# TopLevel.net
KiCad netlist of a schematic drawn in Altium Designer
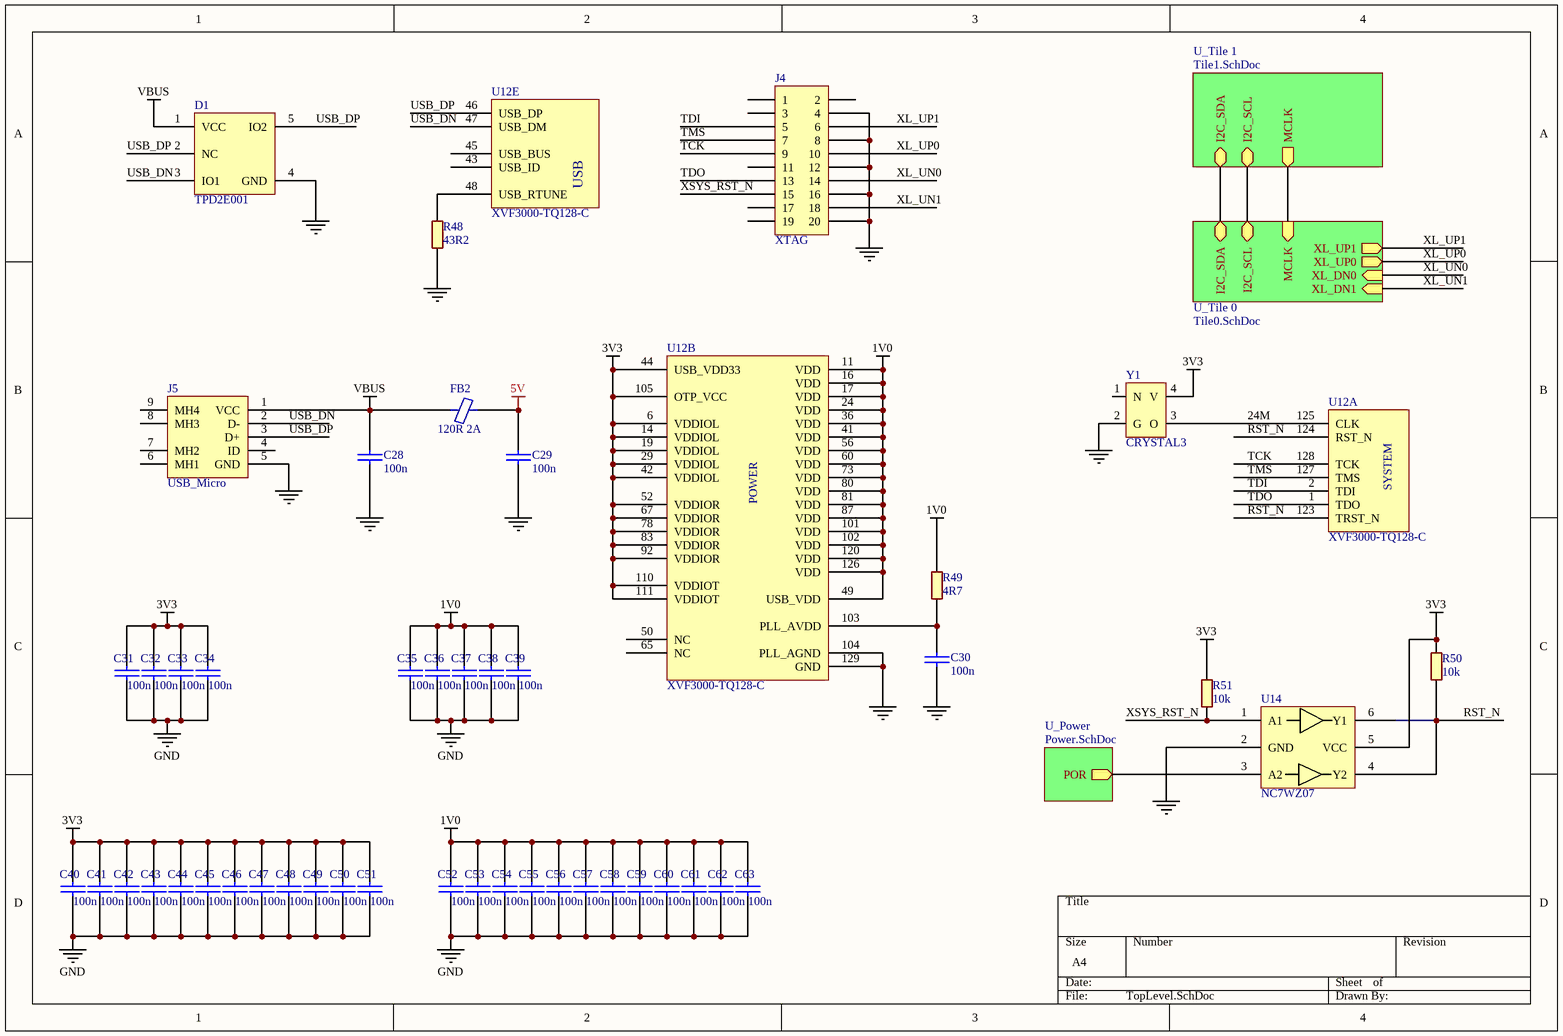
[diagram p0: TopLevel.SchDoc]

(export (version "E")
  (design (tool "Eeschema 10.0.6"))
  (components
    (comp (ref "C28")
      (value "100n")
      (footprint "C0603")
      (description "Capacitor")
      (libsource (lib "Library") (part "CAP"))
    )
    (comp (ref "C29")
      (value "100n")
      (footprint "C0603")
      (description "Capacitor")
      (libsource (lib "Library") (part "CAP"))
    )
    (comp (ref "C30")
      (value "100n")
      (footprint "C0603")
      (description "Capacitor")
      (libsource (lib "Library") (part "CAP"))
    )
    (comp (ref "C31")
      (value "100n")
      (footprint "C0603")
      (description "Capacitor")
      (libsource (lib "Library") (part "CAP"))
    )
    (comp (ref "C32")
      (value "100n")
      (footprint "C0603")
      (description "Capacitor")
      (libsource (lib "Library") (part "CAP"))
    )
    (comp (ref "C33")
      (value "100n")
      (footprint "C0603")
      (description "Capacitor")
      (libsource (lib "Library") (part "CAP"))
    )
    (comp (ref "C34")
      (value "100n")
      (footprint "C0603")
      (description "Capacitor")
      (libsource (lib "Library") (part "CAP"))
    )
    (comp (ref "C35")
      (value "100n")
      (footprint "C0603")
      (description "Capacitor")
      (libsource (lib "Library") (part "CAP"))
    )
    (comp (ref "C36")
      (value "100n")
      (footprint "C0603")
      (description "Capacitor")
      (libsource (lib "Library") (part "CAP"))
    )
    (comp (ref "C37")
      (value "100n")
      (footprint "C0603")
      (description "Capacitor")
      (libsource (lib "Library") (part "CAP"))
    )
    (comp (ref "C38")
      (value "100n")
      (footprint "C0603")
      (description "Capacitor")
      (libsource (lib "Library") (part "CAP"))
    )
    (comp (ref "C39")
      (value "100n")
      (footprint "C0603")
      (description "Capacitor")
      (libsource (lib "Library") (part "CAP"))
    )
    (comp (ref "C40")
      (value "100n")
      (footprint "C0603")
      (description "Capacitor")
      (libsource (lib "Library") (part "CAP"))
    )
    (comp (ref "C41")
      (value "100n")
      (footprint "C0603")
      (description "Capacitor")
      (libsource (lib "Library") (part "CAP"))
    )
    (comp (ref "C42")
      (value "100n")
      (footprint "C0603")
      (description "Capacitor")
      (libsource (lib "Library") (part "CAP"))
    )
    (comp (ref "C43")
      (value "100n")
      (footprint "C0603")
      (description "Capacitor")
      (libsource (lib "Library") (part "CAP"))
    )
    (comp (ref "C44")
      (value "100n")
      (footprint "C0603")
      (description "Capacitor")
      (libsource (lib "Library") (part "CAP"))
    )
    (comp (ref "C45")
      (value "100n")
      (footprint "C0603")
      (description "Capacitor")
      (libsource (lib "Library") (part "CAP"))
    )
    (comp (ref "C46")
      (value "100n")
      (footprint "C0603")
      (description "Capacitor")
      (libsource (lib "Library") (part "CAP"))
    )
    (comp (ref "C47")
      (value "100n")
      (footprint "C0603")
      (description "Capacitor")
      (libsource (lib "Library") (part "CAP"))
    )
    (comp (ref "C48")
      (value "100n")
      (footprint "C0603")
      (description "Capacitor")
      (libsource (lib "Library") (part "CAP"))
    )
    (comp (ref "C49")
      (value "100n")
      (footprint "C0603")
      (description "Capacitor")
      (libsource (lib "Library") (part "CAP"))
    )
    (comp (ref "C50")
      (value "100n")
      (footprint "C0603")
      (description "Capacitor")
      (libsource (lib "Library") (part "CAP"))
    )
    (comp (ref "C51")
      (value "100n")
      (footprint "C0603")
      (description "Capacitor")
      (libsource (lib "Library") (part "CAP"))
    )
    (comp (ref "C52")
      (value "100n")
      (footprint "C0603")
      (description "Capacitor")
      (libsource (lib "Library") (part "CAP"))
    )
    (comp (ref "C53")
      (value "100n")
      (footprint "C0603")
      (description "Capacitor")
      (libsource (lib "Library") (part "CAP"))
    )
    (comp (ref "C54")
      (value "100n")
      (footprint "C0603")
      (description "Capacitor")
      (libsource (lib "Library") (part "CAP"))
    )
    (comp (ref "C55")
      (value "100n")
      (footprint "C0603")
      (description "Capacitor")
      (libsource (lib "Library") (part "CAP"))
    )
    (comp (ref "C56")
      (value "100n")
      (footprint "C0603")
      (description "Capacitor")
      (libsource (lib "Library") (part "CAP"))
    )
    (comp (ref "C57")
      (value "100n")
      (footprint "C0603")
      (description "Capacitor")
      (libsource (lib "Library") (part "CAP"))
    )
    (comp (ref "C58")
      (value "100n")
      (footprint "C0603")
      (description "Capacitor")
      (libsource (lib "Library") (part "CAP"))
    )
    (comp (ref "C59")
      (value "100n")
      (footprint "C0603")
      (description "Capacitor")
      (libsource (lib "Library") (part "CAP"))
    )
    (comp (ref "C60")
      (value "100n")
      (footprint "C0603")
      (description "Capacitor")
      (libsource (lib "Library") (part "CAP"))
    )
    (comp (ref "C61")
      (value "100n")
      (footprint "C0603")
      (description "Capacitor")
      (libsource (lib "Library") (part "CAP"))
    )
    (comp (ref "C62")
      (value "100n")
      (footprint "C0603")
      (description "Capacitor")
      (libsource (lib "Library") (part "CAP"))
    )
    (comp (ref "C63")
      (value "100n")
      (footprint "C0603")
      (description "Capacitor")
      (libsource (lib "Library") (part "CAP"))
    )
    (comp (ref "D1") (value "TPD2E001") (footprint "SOT-5X3") (libsource (lib "Library") (part "TPD2E001")))
    (comp (ref "FB2") (value "120R 2A") (footprint "L0603") (libsource (lib "Library") (part "FB")))
    (comp (ref "J4")
      (value "XTAG")
      (footprint "MHDR2X10")
      (description "Header, 10-Pin, Dual row")
      (fields (field (name "PUBLISHER") "Altium Limited"))
      (libsource (lib "Miscellaneous Connectors") (part "MHDR2X10"))
    )
    (comp (ref "J5")
      (value "USB_Micro")
      (footprint "USB-MICRO5")
      (description "USB micro female SMT with 4 fixed foot")
      (libsource (lib "Library") (part "USB_Micro_5S_B"))
    )
    (comp (ref "R48")
      (value "43R2")
      (footprint "R0603")
      (description "RES")
      (libsource (lib "Library") (part "R"))
    )
    (comp (ref "R49")
      (value "4R7")
      (footprint "R0603")
      (description "RES")
      (libsource (lib "Library") (part "R"))
    )
    (comp (ref "R50")
      (value "10k")
      (footprint "R0603")
      (description "RES")
      (libsource (lib "Library") (part "R"))
    )
    (comp (ref "R51")
      (value "10k")
      (footprint "R0603")
      (description "RES")
      (libsource (lib "Library") (part "R"))
    )
    (comp (ref "U12")
      (value "XVF3000-TQ128-C")
      (footprint "LQFP-128 - VSS")
      (libsource (lib "Library") (part "XVF3000-TQ128-C"))
    )
    (comp (ref "U14") (value "NC7WZ07") (footprint "SC70-6") (libsource (lib "Library") (part "NC7WZ07")))
    (comp (ref "Y1") (value "CRYSTAL3") (footprint "JT3225") (libsource (lib "Library") (part "CRYSTAL3")))
  )
  (nets
    (net (code "1") (name "/24M") (class "Default")
      (node (ref "U12") (pin "125") (pinfunction "CLK_125") (pintype "passive"))
      (node (ref "Y1") (pin "3") (pinfunction "O_3") (pintype "passive"))
    )
    (net (code "5") (name "/POR") (class "Default")
      (node (ref "U14") (pin "3") (pinfunction "A2_3") (pintype "passive"))
    )
    (net (code "6") (name "/RST_N") (class "Default")
      (node (ref "R50") (pin "1") (pinfunction "1_1") (pintype "passive"))
      (node (ref "U12") (pin "123") (pinfunction "TRST_N_123") (pintype "passive"))
      (node (ref "U12") (pin "124") (pinfunction "RST_N_124") (pintype "passive"))
      (node (ref "U14") (pin "4") (pinfunction "Y2_4") (pintype "passive"))
      (node (ref "U14") (pin "6") (pinfunction "Y1_6") (pintype "passive"))
    )
    (net (code "7") (name "/TCK") (class "Default")
      (node (ref "J4") (pin "9") (pinfunction "9_9") (pintype "passive"))
      (node (ref "U12") (pin "128") (pinfunction "TCK_128") (pintype "passive"))
    )
    (net (code "8") (name "/TDI") (class "Default")
      (node (ref "J4") (pin "5") (pinfunction "5_5") (pintype "passive"))
      (node (ref "U12") (pin "2") (pinfunction "TDI_2") (pintype "passive"))
    )
    (net (code "9") (name "/TDO") (class "Default")
      (node (ref "J4") (pin "13") (pinfunction "13_13") (pintype "passive"))
      (node (ref "U12") (pin "1") (pinfunction "TDO_1") (pintype "passive"))
    )
    (net (code "10") (name "/TMS") (class "Default")
      (node (ref "J4") (pin "7") (pinfunction "7_7") (pintype "passive"))
      (node (ref "U12") (pin "127") (pinfunction "TMS_127") (pintype "passive"))
    )
    (net (code "11") (name "/USB_DN") (class "Default")
      (node (ref "D1") (pin "3") (pinfunction "IO1_3") (pintype "passive"))
      (node (ref "J5") (pin "2") (pinfunction "D-_2") (pintype "passive"))
      (node (ref "U12") (pin "47") (pinfunction "USB_DM_47") (pintype "passive"))
    )
    (net (code "12") (name "/USB_DP") (class "Default")
      (node (ref "D1") (pin "2") (pinfunction "NC_2") (pintype "passive"))
      (node (ref "D1") (pin "5") (pinfunction "IO2_5") (pintype "passive"))
      (node (ref "J5") (pin "3") (pinfunction "D+_3") (pintype "passive"))
      (node (ref "U12") (pin "46") (pinfunction "USB_DP_46") (pintype "passive"))
    )
    (net (code "13") (name "/XL_UN0") (class "Default")
      (node (ref "J4") (pin "14") (pinfunction "14_14") (pintype "passive"))
    )
    (net (code "14") (name "/XL_UN1") (class "Default")
      (node (ref "J4") (pin "18") (pinfunction "18_18") (pintype "passive"))
    )
    (net (code "15") (name "/XL_UP0") (class "Default")
      (node (ref "J4") (pin "10") (pinfunction "10_10") (pintype "passive"))
    )
    (net (code "16") (name "/XL_UP1") (class "Default")
      (node (ref "J4") (pin "6") (pinfunction "6_6") (pintype "passive"))
    )
    (net (code "17") (name "/XSYS_RST_N") (class "Default")
      (node (ref "J4") (pin "15") (pinfunction "15_15") (pintype "passive"))
      (node (ref "R51") (pin "1") (pinfunction "1_1") (pintype "passive"))
      (node (ref "U14") (pin "1") (pinfunction "A1_1") (pintype "passive"))
    )
    (net (code "18") (name "1V0") (class "Default")
      (node (ref "C35") (pin "1") (pinfunction "1_1") (pintype "passive"))
      (node (ref "C36") (pin "1") (pinfunction "1_1") (pintype "passive"))
      (node (ref "C37") (pin "1") (pinfunction "1_1") (pintype "passive"))
      (node (ref "C38") (pin "1") (pinfunction "1_1") (pintype "passive"))
      (node (ref "C39") (pin "1") (pinfunction "1_1") (pintype "passive"))
      (node (ref "C52") (pin "1") (pinfunction "1_1") (pintype "passive"))
      (node (ref "C53") (pin "1") (pinfunction "1_1") (pintype "passive"))
      (node (ref "C54") (pin "1") (pinfunction "1_1") (pintype "passive"))
      (node (ref "C55") (pin "1") (pinfunction "1_1") (pintype "passive"))
      (node (ref "C56") (pin "1") (pinfunction "1_1") (pintype "passive"))
      (node (ref "C57") (pin "1") (pinfunction "1_1") (pintype "passive"))
      (node (ref "C58") (pin "1") (pinfunction "1_1") (pintype "passive"))
      (node (ref "C59") (pin "1") (pinfunction "1_1") (pintype "passive"))
      (node (ref "C60") (pin "1") (pinfunction "1_1") (pintype "passive"))
      (node (ref "C61") (pin "1") (pinfunction "1_1") (pintype "passive"))
      (node (ref "C62") (pin "1") (pinfunction "1_1") (pintype "passive"))
      (node (ref "C63") (pin "1") (pinfunction "1_1") (pintype "passive"))
      (node (ref "R49") (pin "2") (pinfunction "2_2") (pintype "passive"))
      (node (ref "U12") (pin "101") (pinfunction "VDD_101") (pintype "passive"))
      (node (ref "U12") (pin "102") (pinfunction "VDD_102") (pintype "passive"))
      (node (ref "U12") (pin "11") (pinfunction "VDD_11") (pintype "passive"))
      (node (ref "U12") (pin "120") (pinfunction "VDD_120") (pintype "passive"))
      (node (ref "U12") (pin "126") (pinfunction "VDD_126") (pintype "passive"))
      (node (ref "U12") (pin "16") (pinfunction "VDD_16") (pintype "passive"))
      (node (ref "U12") (pin "17") (pinfunction "VDD_17") (pintype "passive"))
      (node (ref "U12") (pin "24") (pinfunction "VDD_24") (pintype "passive"))
      (node (ref "U12") (pin "36") (pinfunction "VDD_36") (pintype "passive"))
      (node (ref "U12") (pin "41") (pinfunction "VDD_41") (pintype "passive"))
      (node (ref "U12") (pin "49") (pinfunction "USB_VDD_49") (pintype "passive"))
      (node (ref "U12") (pin "56") (pinfunction "VDD_56") (pintype "passive"))
      (node (ref "U12") (pin "60") (pinfunction "VDD_60") (pintype "passive"))
      (node (ref "U12") (pin "73") (pinfunction "VDD_73") (pintype "passive"))
      (node (ref "U12") (pin "80") (pinfunction "VDD_80") (pintype "passive"))
      (node (ref "U12") (pin "81") (pinfunction "VDD_81") (pintype "passive"))
      (node (ref "U12") (pin "87") (pinfunction "VDD_87") (pintype "passive"))
    )
    (net (code "19") (name "3V3") (class "Default")
      (node (ref "C31") (pin "1") (pinfunction "1_1") (pintype "passive"))
      (node (ref "C32") (pin "1") (pinfunction "1_1") (pintype "passive"))
      (node (ref "C33") (pin "1") (pinfunction "1_1") (pintype "passive"))
      (node (ref "C34") (pin "1") (pinfunction "1_1") (pintype "passive"))
      (node (ref "C40") (pin "1") (pinfunction "1_1") (pintype "passive"))
      (node (ref "C41") (pin "1") (pinfunction "1_1") (pintype "passive"))
      (node (ref "C42") (pin "1") (pinfunction "1_1") (pintype "passive"))
      (node (ref "C43") (pin "1") (pinfunction "1_1") (pintype "passive"))
      (node (ref "C44") (pin "1") (pinfunction "1_1") (pintype "passive"))
      (node (ref "C45") (pin "1") (pinfunction "1_1") (pintype "passive"))
      (node (ref "C46") (pin "1") (pinfunction "1_1") (pintype "passive"))
      (node (ref "C47") (pin "1") (pinfunction "1_1") (pintype "passive"))
      (node (ref "C48") (pin "1") (pinfunction "1_1") (pintype "passive"))
      (node (ref "C49") (pin "1") (pinfunction "1_1") (pintype "passive"))
      (node (ref "C50") (pin "1") (pinfunction "1_1") (pintype "passive"))
      (node (ref "C51") (pin "1") (pinfunction "1_1") (pintype "passive"))
      (node (ref "R50") (pin "2") (pinfunction "2_2") (pintype "passive"))
      (node (ref "R51") (pin "2") (pinfunction "2_2") (pintype "passive"))
      (node (ref "U12") (pin "105") (pinfunction "OTP_VCC_105") (pintype "passive"))
      (node (ref "U12") (pin "110") (pinfunction "VDDIOT_110") (pintype "passive"))
      (node (ref "U12") (pin "111") (pinfunction "VDDIOT_111") (pintype "passive"))
      (node (ref "U12") (pin "14") (pinfunction "VDDIOL_14") (pintype "passive"))
      (node (ref "U12") (pin "19") (pinfunction "VDDIOL_19") (pintype "passive"))
      (node (ref "U12") (pin "29") (pinfunction "VDDIOL_29") (pintype "passive"))
      (node (ref "U12") (pin "42") (pinfunction "VDDIOL_42") (pintype "passive"))
      (node (ref "U12") (pin "44") (pinfunction "USB_VDD33_44") (pintype "passive"))
      (node (ref "U12") (pin "52") (pinfunction "VDDIOR_52") (pintype "passive"))
      (node (ref "U12") (pin "6") (pinfunction "VDDIOL_6") (pintype "passive"))
      (node (ref "U12") (pin "67") (pinfunction "VDDIOR_67") (pintype "passive"))
      (node (ref "U12") (pin "78") (pinfunction "VDDIOR_78") (pintype "passive"))
      (node (ref "U12") (pin "83") (pinfunction "VDDIOR_83") (pintype "passive"))
      (node (ref "U12") (pin "92") (pinfunction "VDDIOR_92") (pintype "passive"))
      (node (ref "U14") (pin "5") (pinfunction "VCC_5") (pintype "passive"))
      (node (ref "Y1") (pin "4") (pinfunction "V_4") (pintype "passive"))
    )
    (net (code "20") (name "5V") (class "Default")
      (node (ref "C29") (pin "1") (pinfunction "1_1") (pintype "passive"))
      (node (ref "FB2") (pin "2") (pinfunction "2_2") (pintype "power_in"))
    )
    (net (code "21") (name "GND") (class "Default")
      (node (ref "C28") (pin "2") (pinfunction "2_2") (pintype "passive"))
      (node (ref "C29") (pin "2") (pinfunction "2_2") (pintype "passive"))
      (node (ref "C30") (pin "2") (pinfunction "2_2") (pintype "passive"))
      (node (ref "C31") (pin "2") (pinfunction "2_2") (pintype "passive"))
      (node (ref "C32") (pin "2") (pinfunction "2_2") (pintype "passive"))
      (node (ref "C33") (pin "2") (pinfunction "2_2") (pintype "passive"))
      (node (ref "C34") (pin "2") (pinfunction "2_2") (pintype "passive"))
      (node (ref "C35") (pin "2") (pinfunction "2_2") (pintype "passive"))
      (node (ref "C36") (pin "2") (pinfunction "2_2") (pintype "passive"))
      (node (ref "C37") (pin "2") (pinfunction "2_2") (pintype "passive"))
      (node (ref "C38") (pin "2") (pinfunction "2_2") (pintype "passive"))
      (node (ref "C39") (pin "2") (pinfunction "2_2") (pintype "passive"))
      (node (ref "C40") (pin "2") (pinfunction "2_2") (pintype "passive"))
      (node (ref "C41") (pin "2") (pinfunction "2_2") (pintype "passive"))
      (node (ref "C42") (pin "2") (pinfunction "2_2") (pintype "passive"))
      (node (ref "C43") (pin "2") (pinfunction "2_2") (pintype "passive"))
      (node (ref "C44") (pin "2") (pinfunction "2_2") (pintype "passive"))
      (node (ref "C45") (pin "2") (pinfunction "2_2") (pintype "passive"))
      (node (ref "C46") (pin "2") (pinfunction "2_2") (pintype "passive"))
      (node (ref "C47") (pin "2") (pinfunction "2_2") (pintype "passive"))
      (node (ref "C48") (pin "2") (pinfunction "2_2") (pintype "passive"))
      (node (ref "C49") (pin "2") (pinfunction "2_2") (pintype "passive"))
      (node (ref "C50") (pin "2") (pinfunction "2_2") (pintype "passive"))
      (node (ref "C51") (pin "2") (pinfunction "2_2") (pintype "passive"))
      (node (ref "C52") (pin "2") (pinfunction "2_2") (pintype "passive"))
      (node (ref "C53") (pin "2") (pinfunction "2_2") (pintype "passive"))
      (node (ref "C54") (pin "2") (pinfunction "2_2") (pintype "passive"))
      (node (ref "C55") (pin "2") (pinfunction "2_2") (pintype "passive"))
      (node (ref "C56") (pin "2") (pinfunction "2_2") (pintype "passive"))
      (node (ref "C57") (pin "2") (pinfunction "2_2") (pintype "passive"))
      (node (ref "C58") (pin "2") (pinfunction "2_2") (pintype "passive"))
      (node (ref "C59") (pin "2") (pinfunction "2_2") (pintype "passive"))
      (node (ref "C60") (pin "2") (pinfunction "2_2") (pintype "passive"))
      (node (ref "C61") (pin "2") (pinfunction "2_2") (pintype "passive"))
      (node (ref "C62") (pin "2") (pinfunction "2_2") (pintype "passive"))
      (node (ref "C63") (pin "2") (pinfunction "2_2") (pintype "passive"))
      (node (ref "D1") (pin "4") (pinfunction "GND_4") (pintype "passive"))
      (node (ref "J4") (pin "12") (pinfunction "12_12") (pintype "passive"))
      (node (ref "J4") (pin "16") (pinfunction "16_16") (pintype "passive"))
      (node (ref "J4") (pin "20") (pinfunction "20_20") (pintype "passive"))
      (node (ref "J4") (pin "4") (pinfunction "4_4") (pintype "passive"))
      (node (ref "J4") (pin "8") (pinfunction "8_8") (pintype "passive"))
      (node (ref "J5") (pin "5") (pinfunction "GND_5") (pintype "passive"))
      (node (ref "R48") (pin "1") (pinfunction "1_1") (pintype "passive"))
      (node (ref "U12") (pin "104") (pinfunction "PLL_AGND_104") (pintype "passive"))
      (node (ref "U12") (pin "129") (pinfunction "GND_129") (pintype "passive"))
      (node (ref "U14") (pin "2") (pinfunction "GND_2") (pintype "passive"))
      (node (ref "Y1") (pin "2") (pinfunction "G_2") (pintype "passive"))
    )
    (net (code "22") (name "Net-(U12B-PLL_AVDD)") (class "Default")
      (node (ref "C30") (pin "1") (pinfunction "1_1") (pintype "passive"))
      (node (ref "R49") (pin "1") (pinfunction "1_1") (pintype "passive"))
      (node (ref "U12") (pin "103") (pinfunction "PLL_AVDD_103") (pintype "passive"))
    )
    (net (code "23") (name "Net-(U12E-USB_RTUNE)") (class "Default")
      (node (ref "R48") (pin "2") (pinfunction "2_2") (pintype "passive"))
      (node (ref "U12") (pin "48") (pinfunction "USB_RTUNE_48") (pintype "passive"))
    )
    (net (code "24") (name "VBUS") (class "Default")
      (node (ref "C28") (pin "1") (pinfunction "1_1") (pintype "passive"))
      (node (ref "D1") (pin "1") (pinfunction "VCC_1") (pintype "passive"))
      (node (ref "FB2") (pin "1") (pinfunction "1_1") (pintype "power_in"))
      (node (ref "J5") (pin "1") (pinfunction "VCC_1") (pintype "passive"))
    )
    (net (code "25") (name "unconnected-(J4-Pad1)") (class "Default")
      (node (ref "J4") (pin "1") (pinfunction "1_1") (pintype "passive"))
    )
    (net (code "26") (name "unconnected-(J4-Pad2)") (class "Default")
      (node (ref "J4") (pin "2") (pinfunction "2_2") (pintype "passive"))
    )
    (net (code "27") (name "unconnected-(J4-Pad3)") (class "Default")
      (node (ref "J4") (pin "3") (pinfunction "3_3") (pintype "passive"))
    )
    (net (code "28") (name "unconnected-(J4-Pad11)") (class "Default")
      (node (ref "J4") (pin "11") (pinfunction "11_11") (pintype "passive"))
    )
    (net (code "29") (name "unconnected-(J4-Pad17)") (class "Default")
      (node (ref "J4") (pin "17") (pinfunction "17_17") (pintype "passive"))
    )
    (net (code "30") (name "unconnected-(J4-Pad19)") (class "Default")
      (node (ref "J4") (pin "19") (pinfunction "19_19") (pintype "passive"))
    )
    (net (code "31") (name "unconnected-(J5-ID-Pad4)") (class "Default")
      (node (ref "J5") (pin "4") (pinfunction "ID_4") (pintype "passive"))
    )
    (net (code "32") (name "unconnected-(J5-MH1-Pad6)") (class "Default")
      (node (ref "J5") (pin "6") (pinfunction "MH1_6") (pintype "passive"))
    )
    (net (code "33") (name "unconnected-(J5-MH2-Pad7)") (class "Default")
      (node (ref "J5") (pin "7") (pinfunction "MH2_7") (pintype "passive"))
    )
    (net (code "34") (name "unconnected-(J5-MH3-Pad8)") (class "Default")
      (node (ref "J5") (pin "8") (pinfunction "MH3_8") (pintype "passive"))
    )
    (net (code "35") (name "unconnected-(J5-MH4-Pad9)") (class "Default")
      (node (ref "J5") (pin "9") (pinfunction "MH4_9") (pintype "passive"))
    )
    (net (code "36") (name "unconnected-(U12B-NC-Pad50)") (class "Default")
      (node (ref "U12") (pin "50") (pinfunction "NC_50") (pintype "passive"))
    )
    (net (code "37") (name "unconnected-(U12B-NC-Pad65)") (class "Default")
      (node (ref "U12") (pin "65") (pinfunction "NC_65") (pintype "passive"))
    )
    (net (code "38") (name "unconnected-(U12E-USB_BUS-Pad45)") (class "Default")
      (node (ref "U12") (pin "45") (pinfunction "USB_BUS_45") (pintype "passive"))
    )
    (net (code "39") (name "unconnected-(U12E-USB_ID-Pad43)") (class "Default")
      (node (ref "U12") (pin "43") (pinfunction "USB_ID_43") (pintype "passive"))
    )
    (net (code "40") (name "unconnected-(Y1-N-Pad1)") (class "Default")
      (node (ref "Y1") (pin "1") (pinfunction "N_1") (pintype "passive"))
    )
  )
)
